# Ring_4_C.net
KiCad netlist of a schematic drawn in Altium Designer
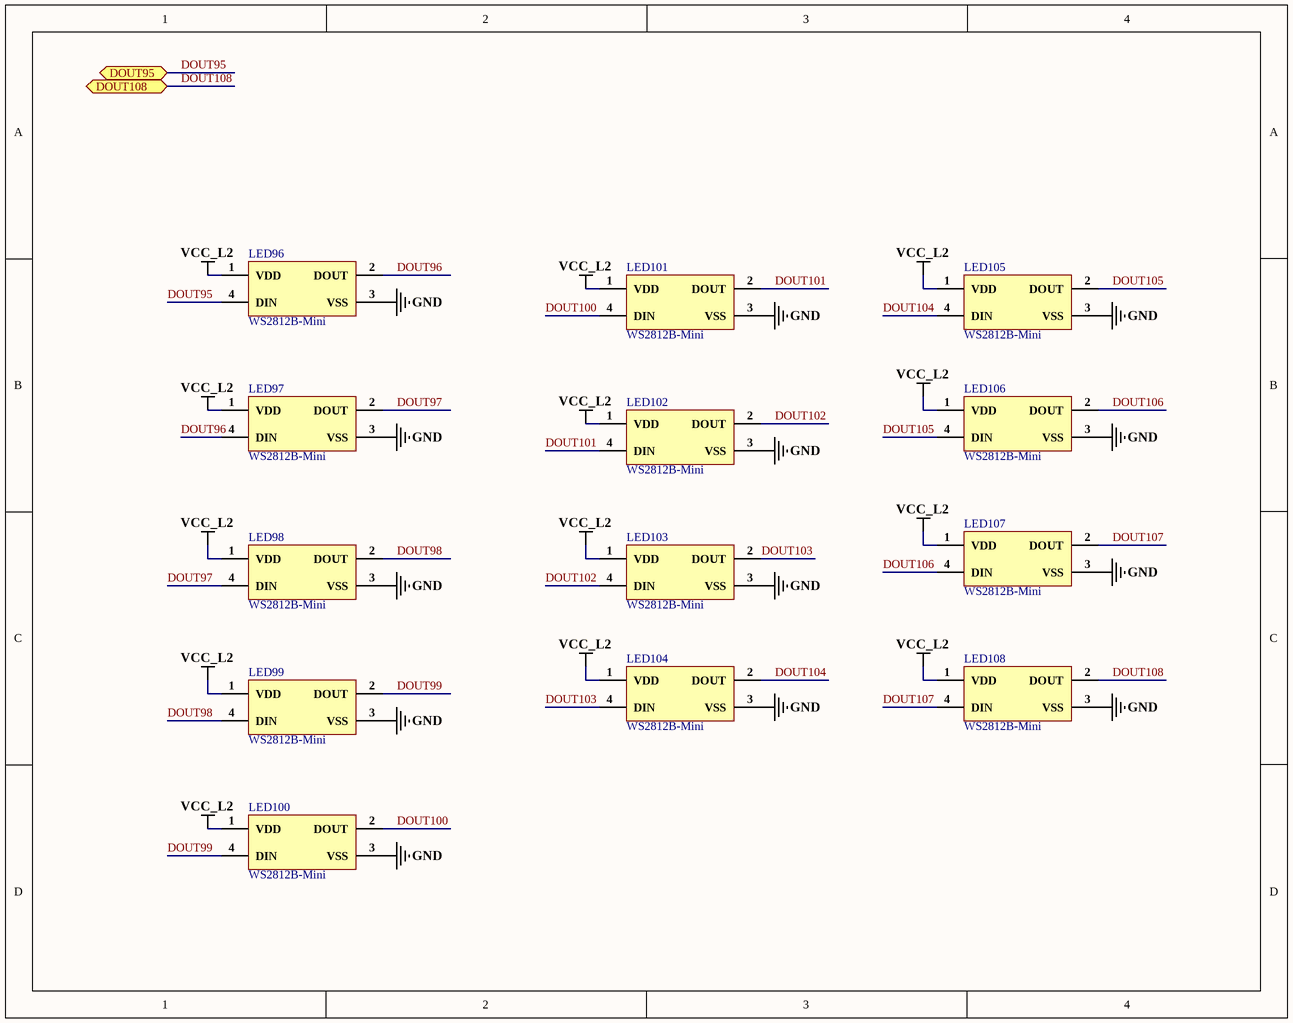
[diagram p0: Ring 4_C.SchDoc]

(export (version "E")
  (design (tool "Eeschema 10.0.6"))
  (components
    (comp (ref "LED96")
      (value "WS2812B-Mini")
      (footprint "WS2812B-Mini")
      (description "SMD,3.5x3.5mm Light Emitting Diodes (LED) RoHS")
      (fields (field (name "MANUFACTURER") "Worldsemi"))
      (libsource (lib "TT_IntLib") (part "WS2812B-Mini"))
    )
    (comp (ref "LED97")
      (value "WS2812B-Mini")
      (footprint "WS2812B-Mini")
      (description "SMD,3.5x3.5mm Light Emitting Diodes (LED) RoHS")
      (fields (field (name "MANUFACTURER") "Worldsemi"))
      (libsource (lib "TT_IntLib") (part "WS2812B-Mini"))
    )
    (comp (ref "LED98")
      (value "WS2812B-Mini")
      (footprint "WS2812B-Mini")
      (description "SMD,3.5x3.5mm Light Emitting Diodes (LED) RoHS")
      (fields (field (name "MANUFACTURER") "Worldsemi"))
      (libsource (lib "TT_IntLib") (part "WS2812B-Mini"))
    )
    (comp (ref "LED99")
      (value "WS2812B-Mini")
      (footprint "WS2812B-Mini")
      (description "SMD,3.5x3.5mm Light Emitting Diodes (LED) RoHS")
      (fields (field (name "MANUFACTURER") "Worldsemi"))
      (libsource (lib "TT_IntLib") (part "WS2812B-Mini"))
    )
    (comp (ref "LED100")
      (value "WS2812B-Mini")
      (footprint "WS2812B-Mini")
      (description "SMD,3.5x3.5mm Light Emitting Diodes (LED) RoHS")
      (fields (field (name "MANUFACTURER") "Worldsemi"))
      (libsource (lib "TT_IntLib") (part "WS2812B-Mini"))
    )
    (comp (ref "LED101")
      (value "WS2812B-Mini")
      (footprint "WS2812B-Mini")
      (description "SMD,3.5x3.5mm Light Emitting Diodes (LED) RoHS")
      (fields (field (name "MANUFACTURER") "Worldsemi"))
      (libsource (lib "TT_IntLib") (part "WS2812B-Mini"))
    )
    (comp (ref "LED102")
      (value "WS2812B-Mini")
      (footprint "WS2812B-Mini")
      (description "SMD,3.5x3.5mm Light Emitting Diodes (LED) RoHS")
      (fields (field (name "MANUFACTURER") "Worldsemi"))
      (libsource (lib "TT_IntLib") (part "WS2812B-Mini"))
    )
    (comp (ref "LED103")
      (value "WS2812B-Mini")
      (footprint "WS2812B-Mini")
      (description "SMD,3.5x3.5mm Light Emitting Diodes (LED) RoHS")
      (fields (field (name "MANUFACTURER") "Worldsemi"))
      (libsource (lib "TT_IntLib") (part "WS2812B-Mini"))
    )
    (comp (ref "LED104")
      (value "WS2812B-Mini")
      (footprint "WS2812B-Mini")
      (description "SMD,3.5x3.5mm Light Emitting Diodes (LED) RoHS")
      (fields (field (name "MANUFACTURER") "Worldsemi"))
      (libsource (lib "TT_IntLib") (part "WS2812B-Mini"))
    )
    (comp (ref "LED105")
      (value "WS2812B-Mini")
      (footprint "WS2812B-Mini")
      (description "SMD,3.5x3.5mm Light Emitting Diodes (LED) RoHS")
      (fields (field (name "MANUFACTURER") "Worldsemi"))
      (libsource (lib "TT_IntLib") (part "WS2812B-Mini"))
    )
    (comp (ref "LED106")
      (value "WS2812B-Mini")
      (footprint "WS2812B-Mini")
      (description "SMD,3.5x3.5mm Light Emitting Diodes (LED) RoHS")
      (fields (field (name "MANUFACTURER") "Worldsemi"))
      (libsource (lib "TT_IntLib") (part "WS2812B-Mini"))
    )
    (comp (ref "LED107")
      (value "WS2812B-Mini")
      (footprint "WS2812B-Mini")
      (description "SMD,3.5x3.5mm Light Emitting Diodes (LED) RoHS")
      (fields (field (name "MANUFACTURER") "Worldsemi"))
      (libsource (lib "TT_IntLib") (part "WS2812B-Mini"))
    )
    (comp (ref "LED108")
      (value "WS2812B-Mini")
      (footprint "WS2812B-Mini")
      (description "SMD,3.5x3.5mm Light Emitting Diodes (LED) RoHS")
      (fields (field (name "MANUFACTURER") "Worldsemi"))
      (libsource (lib "TT_IntLib") (part "WS2812B-Mini"))
    )
  )
  (nets
    (net (code "1") (name "/DOUT95") (class "Default")
      (node (ref "LED96") (pin "4") (pinfunction "DIN_4") (pintype "passive"))
    )
    (net (code "2") (name "/DOUT96") (class "Default")
      (node (ref "LED96") (pin "2") (pinfunction "DOUT_2") (pintype "passive"))
      (node (ref "LED97") (pin "4") (pinfunction "DIN_4") (pintype "passive"))
    )
    (net (code "3") (name "/DOUT97") (class "Default")
      (node (ref "LED97") (pin "2") (pinfunction "DOUT_2") (pintype "passive"))
      (node (ref "LED98") (pin "4") (pinfunction "DIN_4") (pintype "passive"))
    )
    (net (code "4") (name "/DOUT98") (class "Default")
      (node (ref "LED98") (pin "2") (pinfunction "DOUT_2") (pintype "passive"))
      (node (ref "LED99") (pin "4") (pinfunction "DIN_4") (pintype "passive"))
    )
    (net (code "5") (name "/DOUT99") (class "Default")
      (node (ref "LED100") (pin "4") (pinfunction "DIN_4") (pintype "passive"))
      (node (ref "LED99") (pin "2") (pinfunction "DOUT_2") (pintype "passive"))
    )
    (net (code "6") (name "/DOUT100") (class "Default")
      (node (ref "LED100") (pin "2") (pinfunction "DOUT_2") (pintype "passive"))
      (node (ref "LED101") (pin "4") (pinfunction "DIN_4") (pintype "passive"))
    )
    (net (code "7") (name "/DOUT101") (class "Default")
      (node (ref "LED101") (pin "2") (pinfunction "DOUT_2") (pintype "passive"))
      (node (ref "LED102") (pin "4") (pinfunction "DIN_4") (pintype "passive"))
    )
    (net (code "8") (name "/DOUT102") (class "Default")
      (node (ref "LED102") (pin "2") (pinfunction "DOUT_2") (pintype "passive"))
      (node (ref "LED103") (pin "4") (pinfunction "DIN_4") (pintype "passive"))
    )
    (net (code "9") (name "/DOUT103") (class "Default")
      (node (ref "LED103") (pin "2") (pinfunction "DOUT_2") (pintype "passive"))
      (node (ref "LED104") (pin "4") (pinfunction "DIN_4") (pintype "passive"))
    )
    (net (code "10") (name "/DOUT104") (class "Default")
      (node (ref "LED104") (pin "2") (pinfunction "DOUT_2") (pintype "passive"))
      (node (ref "LED105") (pin "4") (pinfunction "DIN_4") (pintype "passive"))
    )
    (net (code "11") (name "/DOUT105") (class "Default")
      (node (ref "LED105") (pin "2") (pinfunction "DOUT_2") (pintype "passive"))
      (node (ref "LED106") (pin "4") (pinfunction "DIN_4") (pintype "passive"))
    )
    (net (code "12") (name "/DOUT106") (class "Default")
      (node (ref "LED106") (pin "2") (pinfunction "DOUT_2") (pintype "passive"))
      (node (ref "LED107") (pin "4") (pinfunction "DIN_4") (pintype "passive"))
    )
    (net (code "13") (name "/DOUT107") (class "Default")
      (node (ref "LED107") (pin "2") (pinfunction "DOUT_2") (pintype "passive"))
      (node (ref "LED108") (pin "4") (pinfunction "DIN_4") (pintype "passive"))
    )
    (net (code "14") (name "/DOUT108") (class "Default")
      (node (ref "LED108") (pin "2") (pinfunction "DOUT_2") (pintype "passive"))
    )
    (net (code "15") (name "GND") (class "Default")
      (node (ref "LED100") (pin "3") (pinfunction "VSS_3") (pintype "passive"))
      (node (ref "LED101") (pin "3") (pinfunction "VSS_3") (pintype "passive"))
      (node (ref "LED102") (pin "3") (pinfunction "VSS_3") (pintype "passive"))
      (node (ref "LED103") (pin "3") (pinfunction "VSS_3") (pintype "passive"))
      (node (ref "LED104") (pin "3") (pinfunction "VSS_3") (pintype "passive"))
      (node (ref "LED105") (pin "3") (pinfunction "VSS_3") (pintype "passive"))
      (node (ref "LED106") (pin "3") (pinfunction "VSS_3") (pintype "passive"))
      (node (ref "LED107") (pin "3") (pinfunction "VSS_3") (pintype "passive"))
      (node (ref "LED108") (pin "3") (pinfunction "VSS_3") (pintype "passive"))
      (node (ref "LED96") (pin "3") (pinfunction "VSS_3") (pintype "passive"))
      (node (ref "LED97") (pin "3") (pinfunction "VSS_3") (pintype "passive"))
      (node (ref "LED98") (pin "3") (pinfunction "VSS_3") (pintype "passive"))
      (node (ref "LED99") (pin "3") (pinfunction "VSS_3") (pintype "passive"))
    )
    (net (code "16") (name "VCC_L2") (class "Default")
      (node (ref "LED100") (pin "1") (pinfunction "VDD_1") (pintype "passive"))
      (node (ref "LED101") (pin "1") (pinfunction "VDD_1") (pintype "passive"))
      (node (ref "LED102") (pin "1") (pinfunction "VDD_1") (pintype "passive"))
      (node (ref "LED103") (pin "1") (pinfunction "VDD_1") (pintype "passive"))
      (node (ref "LED104") (pin "1") (pinfunction "VDD_1") (pintype "passive"))
      (node (ref "LED105") (pin "1") (pinfunction "VDD_1") (pintype "passive"))
      (node (ref "LED106") (pin "1") (pinfunction "VDD_1") (pintype "passive"))
      (node (ref "LED107") (pin "1") (pinfunction "VDD_1") (pintype "passive"))
      (node (ref "LED108") (pin "1") (pinfunction "VDD_1") (pintype "passive"))
      (node (ref "LED96") (pin "1") (pinfunction "VDD_1") (pintype "passive"))
      (node (ref "LED97") (pin "1") (pinfunction "VDD_1") (pintype "passive"))
      (node (ref "LED98") (pin "1") (pinfunction "VDD_1") (pintype "passive"))
      (node (ref "LED99") (pin "1") (pinfunction "VDD_1") (pintype "passive"))
    )
  )
)
